# motadora.net
KiCad netlist of a schematic drawn in EAGLE
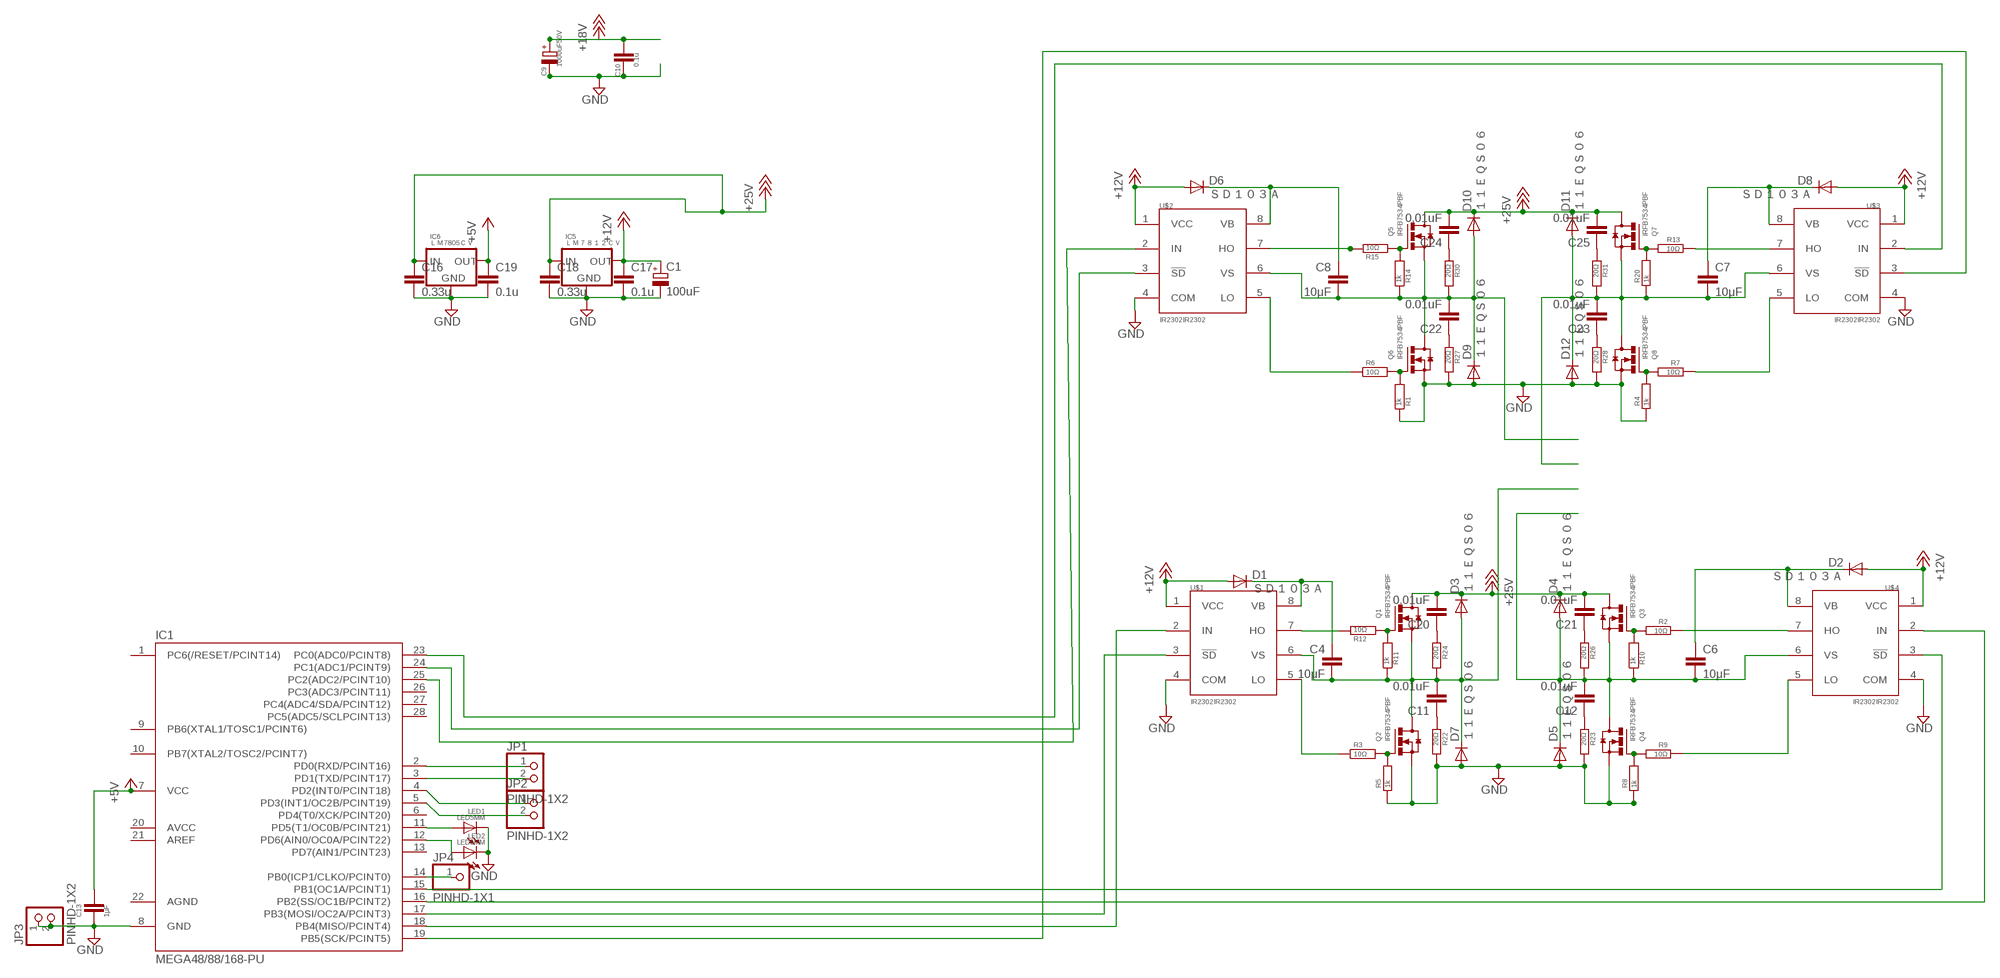
[diagram p0: schematic, sheet 1]

(export (version "E")
  (design (tool "Eeschema 10.0.6"))
  (components
    (comp (ref "C1")
      (value "100uF")
      (footprint "eagle-import:TT2D6")
      (libsource (lib "eagle-import") (part "CPOL-EUTT2D6"))
    )
    (comp (ref "C4")
      (value "10μF")
      (footprint "eagle-import:C025-025X050")
      (libsource (lib "eagle-import") (part "C-EU025-025X050"))
    )
    (comp (ref "C6")
      (value "10μF")
      (footprint "eagle-import:C025-025X050")
      (libsource (lib "eagle-import") (part "C-EU025-025X050"))
    )
    (comp (ref "C7")
      (value "10μF")
      (footprint "eagle-import:C025-025X050")
      (libsource (lib "eagle-import") (part "C-EU025-025X050"))
    )
    (comp (ref "C8")
      (value "10μF")
      (footprint "eagle-import:C025-025X050")
      (libsource (lib "eagle-import") (part "C-EU025-025X050"))
    )
    (comp (ref "C9")
      (value "1000uF50V")
      (footprint "eagle-import:E2,5-7")
      (libsource (lib "eagle-import") (part "CPOL-E2.5-7"))
    )
    (comp (ref "C10")
      (value "0.1u")
      (footprint "eagle-import:C025-025X050")
      (libsource (lib "eagle-import") (part "C-025-025X050"))
    )
    (comp (ref "C11")
      (value "0.01uF")
      (footprint "eagle-import:C025-024X044")
      (libsource (lib "eagle-import") (part "_resistor(抵抗)_C-EU025-024X044"))
    )
    (comp (ref "C12")
      (value "0.01uF")
      (footprint "eagle-import:C025-024X044")
      (libsource (lib "eagle-import") (part "_resistor(抵抗)_C-EU025-024X044"))
    )
    (comp (ref "C13")
      (value "1μF")
      (footprint "eagle-import:C025-025X050")
      (libsource (lib "eagle-import") (part "C{gt}{gt}025-025X050"))
    )
    (comp (ref "C16")
      (value "0.33u")
      (footprint "eagle-import:C025-025X050")
      (libsource (lib "eagle-import") (part "_resistor(抵抗)_C-EU025-025X050"))
    )
    (comp (ref "C17")
      (value "0.1u")
      (footprint "eagle-import:C025-025X050")
      (libsource (lib "eagle-import") (part "_resistor(抵抗)_C-EU025-025X050"))
    )
    (comp (ref "C18")
      (value "0.33u")
      (footprint "eagle-import:C025-025X050")
      (libsource (lib "eagle-import") (part "_resistor(抵抗)_C-EU025-025X050"))
    )
    (comp (ref "C19")
      (value "0.1u")
      (footprint "eagle-import:C025-025X050")
      (libsource (lib "eagle-import") (part "_resistor(抵抗)_C-EU025-025X050"))
    )
    (comp (ref "C20")
      (value "0.01uF")
      (footprint "eagle-import:C025-024X044")
      (libsource (lib "eagle-import") (part "_resistor(抵抗)_C-EU025-024X044"))
    )
    (comp (ref "C21")
      (value "0.01uF")
      (footprint "eagle-import:C025-024X044")
      (libsource (lib "eagle-import") (part "_resistor(抵抗)_C-EU025-024X044"))
    )
    (comp (ref "C22")
      (value "0.01uF")
      (footprint "eagle-import:C025-024X044")
      (libsource (lib "eagle-import") (part "_resistor(抵抗)_C-EU025-024X044"))
    )
    (comp (ref "C23")
      (value "0.01uF")
      (footprint "eagle-import:C025-024X044")
      (libsource (lib "eagle-import") (part "_resistor(抵抗)_C-EU025-024X044"))
    )
    (comp (ref "C24")
      (value "0.01uF")
      (footprint "eagle-import:C025-024X044")
      (libsource (lib "eagle-import") (part "_resistor(抵抗)_C-EU025-024X044"))
    )
    (comp (ref "C25")
      (value "0.01uF")
      (footprint "eagle-import:C025-024X044")
      (libsource (lib "eagle-import") (part "_resistor(抵抗)_C-EU025-024X044"))
    )
    (comp (ref "D1")
      (value "ＳＤ１０３Ａ")
      (footprint "eagle-import:D-5")
      (libsource (lib "eagle-import") (part "DIODE-D-5"))
    )
    (comp (ref "D2")
      (value "ＳＤ１０３Ａ")
      (footprint "eagle-import:D-5")
      (libsource (lib "eagle-import") (part "DIODE-D-5"))
    )
    (comp (ref "D3")
      (value "１１ＥＱＳ０６")
      (footprint "eagle-import:D-5")
      (libsource (lib "eagle-import") (part "DIODE-D-5"))
    )
    (comp (ref "D4")
      (value "１１ＥＱＳ０６")
      (footprint "eagle-import:D-5")
      (libsource (lib "eagle-import") (part "DIODE-D-5"))
    )
    (comp (ref "D5")
      (value "１１ＥＱＳ０６")
      (footprint "eagle-import:D-5")
      (libsource (lib "eagle-import") (part "DIODE-D-5"))
    )
    (comp (ref "D6")
      (value "ＳＤ１０３Ａ")
      (footprint "eagle-import:D-5")
      (libsource (lib "eagle-import") (part "DIODE-D-5"))
    )
    (comp (ref "D7")
      (value "１１ＥＱＳ０６")
      (footprint "eagle-import:D-5")
      (libsource (lib "eagle-import") (part "DIODE-D-5"))
    )
    (comp (ref "D8")
      (value "ＳＤ１０３Ａ")
      (footprint "eagle-import:D-5")
      (libsource (lib "eagle-import") (part "DIODE-D-5"))
    )
    (comp (ref "D9")
      (value "１１ＥＱＳ０６")
      (footprint "eagle-import:D-5")
      (libsource (lib "eagle-import") (part "DIODE-D-5"))
    )
    (comp (ref "D10")
      (value "１１ＥＱＳ０６")
      (footprint "eagle-import:D-5")
      (libsource (lib "eagle-import") (part "DIODE-D-5"))
    )
    (comp (ref "D11")
      (value "１１ＥＱＳ０６")
      (footprint "eagle-import:D-5")
      (libsource (lib "eagle-import") (part "DIODE-D-5"))
    )
    (comp (ref "D12")
      (value "１１ＥＱＳ０６")
      (footprint "eagle-import:D-5")
      (libsource (lib "eagle-import") (part "DIODE-D-5"))
    )
    (comp (ref "IC1")
      (value "MEGA48/88/168-PU")
      (footprint "eagle-import:DIL28-3")
      (libsource (lib "eagle-import") (part "MEGA48/88/168-PU"))
    )
    (comp (ref "IC5")
      (value "ＬＭ７８１２ＣＶ")
      (footprint "eagle-import:TO-92")
      (libsource (lib "eagle-import") (part "V_REG{gt}{gt}TO-92"))
    )
    (comp (ref "IC6")
      (value "ＬＭ7805ＣＶ")
      (footprint "eagle-import:TO-92")
      (libsource (lib "eagle-import") (part "V_REG{gt}{gt}TO-92"))
    )
    (comp (ref "JP1")
      (value "PINHD-1X2")
      (footprint "eagle-import:1X02")
      (libsource (lib "eagle-import") (part "PINHD-1X2"))
    )
    (comp (ref "JP2")
      (value "PINHD-1X2")
      (footprint "eagle-import:1X02")
      (libsource (lib "eagle-import") (part "PINHD-1X2"))
    )
    (comp (ref "JP3")
      (value "PINHD-1X2")
      (footprint "eagle-import:1X02")
      (libsource (lib "eagle-import") (part "PINHD-1X2"))
    )
    (comp (ref "JP4")
      (value "PINHD-1X1")
      (footprint "eagle-import:1X01")
      (libsource (lib "eagle-import") (part "PINHD-1X1"))
    )
    (comp (ref "LED1")
      (value "LED5MM")
      (footprint "eagle-import:LED5MM")
      (libsource (lib "eagle-import") (part "LED5MM"))
    )
    (comp (ref "LED2")
      (value "LED5MM")
      (footprint "eagle-import:LED5MM")
      (libsource (lib "eagle-import") (part "LED5MM"))
    )
    (comp (ref "Q1")
      (value "IRFB7534PBF")
      (footprint "eagle-import:TO220_2")
      (libsource (lib "eagle-import") (part "MOS-FET_NTO-220_2"))
    )
    (comp (ref "Q2")
      (value "IRFB7534PBF")
      (footprint "eagle-import:TO220_2")
      (libsource (lib "eagle-import") (part "MOS-FET_NTO-220_2"))
    )
    (comp (ref "Q3")
      (value "IRFB7534PBF")
      (footprint "eagle-import:TO220_2")
      (libsource (lib "eagle-import") (part "MOS-FET_NTO-220_2"))
    )
    (comp (ref "Q4")
      (value "IRFB7534PBF")
      (footprint "eagle-import:TO220_2")
      (libsource (lib "eagle-import") (part "MOS-FET_NTO-220_2"))
    )
    (comp (ref "Q5")
      (value "IRFB7534PBF")
      (footprint "eagle-import:TO220_2")
      (libsource (lib "eagle-import") (part "MOS-FET_NTO-220_2"))
    )
    (comp (ref "Q6")
      (value "IRFB7534PBF")
      (footprint "eagle-import:TO220_2")
      (libsource (lib "eagle-import") (part "MOS-FET_NTO-220_2"))
    )
    (comp (ref "Q7")
      (value "IRFB7534PBF")
      (footprint "eagle-import:TO220_2")
      (libsource (lib "eagle-import") (part "MOS-FET_NTO-220_2"))
    )
    (comp (ref "Q8")
      (value "IRFB7534PBF")
      (footprint "eagle-import:TO220_2")
      (libsource (lib "eagle-import") (part "MOS-FET_NTO-220_2"))
    )
    (comp (ref "R1")
      (value "1k")
      (footprint "eagle-import:1_4W(8MM)")
      (libsource (lib "eagle-import") (part "R-EU_1/4W(8MM)"))
    )
    (comp (ref "R2")
      (value "10Ω")
      (footprint "eagle-import:1_4W(2.5MM)_")
      (libsource (lib "eagle-import") (part "R-EU_1/4W(2.5MM)_"))
    )
    (comp (ref "R3")
      (value "10Ω")
      (footprint "eagle-import:1_4W(2.5MM)_")
      (libsource (lib "eagle-import") (part "R-EU_1/4W(2.5MM)_"))
    )
    (comp (ref "R4")
      (value "1k")
      (footprint "eagle-import:1_4W(8MM)")
      (libsource (lib "eagle-import") (part "R-EU_1/4W(8MM)"))
    )
    (comp (ref "R5")
      (value "1k")
      (footprint "eagle-import:1_4W(8MM)")
      (libsource (lib "eagle-import") (part "R-EU_1/4W(8MM)"))
    )
    (comp (ref "R6")
      (value "10Ω")
      (footprint "eagle-import:1_4W(2.5MM)_")
      (libsource (lib "eagle-import") (part "R-EU_1/4W(2.5MM)_"))
    )
    (comp (ref "R7")
      (value "10Ω")
      (footprint "eagle-import:1_4W(2.5MM)_")
      (libsource (lib "eagle-import") (part "R-EU_1/4W(2.5MM)_"))
    )
    (comp (ref "R8")
      (value "1k")
      (footprint "eagle-import:1_4W(8MM)")
      (libsource (lib "eagle-import") (part "R-EU_1/4W(8MM)"))
    )
    (comp (ref "R9")
      (value "10Ω")
      (footprint "eagle-import:1_4W(2.5MM)_")
      (libsource (lib "eagle-import") (part "R-EU_1/4W(2.5MM)_"))
    )
    (comp (ref "R10")
      (value "1k")
      (footprint "eagle-import:1_4W(8MM)")
      (libsource (lib "eagle-import") (part "R-EU_1/4W(8MM)"))
    )
    (comp (ref "R11")
      (value "1k")
      (footprint "eagle-import:1_4W(8MM)")
      (libsource (lib "eagle-import") (part "R-EU_1/4W(8MM)"))
    )
    (comp (ref "R12")
      (value "10Ω")
      (footprint "eagle-import:1_4W(2.5MM)_")
      (libsource (lib "eagle-import") (part "R-EU_1/4W(2.5MM)_"))
    )
    (comp (ref "R13")
      (value "10Ω")
      (footprint "eagle-import:1_4W(2.5MM)_")
      (libsource (lib "eagle-import") (part "R-EU_1/4W(2.5MM)_"))
    )
    (comp (ref "R14")
      (value "1k")
      (footprint "eagle-import:1_4W(8MM)")
      (libsource (lib "eagle-import") (part "R-EU_1/4W(8MM)"))
    )
    (comp (ref "R15")
      (value "10Ω")
      (footprint "eagle-import:1_4W(2.5MM)_")
      (libsource (lib "eagle-import") (part "R-EU_1/4W(2.5MM)_"))
    )
    (comp (ref "R20")
      (value "1k")
      (footprint "eagle-import:1_4W(8MM)")
      (libsource (lib "eagle-import") (part "R-EU_1/4W(8MM)"))
    )
    (comp (ref "R22")
      (value "20Ω")
      (footprint "eagle-import:1_4W(2.5MM)_")
      (libsource (lib "eagle-import") (part "R-EU_1/4W(2.5MM)_"))
    )
    (comp (ref "R23")
      (value "20Ω")
      (footprint "eagle-import:1_4W(2.5MM)_")
      (libsource (lib "eagle-import") (part "R-EU_1/4W(2.5MM)_"))
    )
    (comp (ref "R24")
      (value "20Ω")
      (footprint "eagle-import:1_4W(2.5MM)_")
      (libsource (lib "eagle-import") (part "R-EU_1/4W(2.5MM)_"))
    )
    (comp (ref "R26")
      (value "20Ω")
      (footprint "eagle-import:1_4W(2.5MM)_")
      (libsource (lib "eagle-import") (part "R-EU_1/4W(2.5MM)_"))
    )
    (comp (ref "R27")
      (value "20Ω")
      (footprint "eagle-import:1_4W(2.5MM)_")
      (libsource (lib "eagle-import") (part "R-EU_1/4W(2.5MM)_"))
    )
    (comp (ref "R28")
      (value "20Ω")
      (footprint "eagle-import:1_4W(2.5MM)_")
      (libsource (lib "eagle-import") (part "R-EU_1/4W(2.5MM)_"))
    )
    (comp (ref "R30")
      (value "20Ω")
      (footprint "eagle-import:1_4W(2.5MM)_")
      (libsource (lib "eagle-import") (part "R-EU_1/4W(2.5MM)_"))
    )
    (comp (ref "R31")
      (value "20Ω")
      (footprint "eagle-import:1_4W(2.5MM)_")
      (libsource (lib "eagle-import") (part "R-EU_1/4W(2.5MM)_"))
    )
    (comp (ref "U$1")
      (value "IR2302IR2302")
      (footprint "eagle-import:DIL08")
      (libsource (lib "eagle-import") (part "IR2302IR2302"))
    )
    (comp (ref "U$2")
      (value "IR2302IR2302")
      (footprint "eagle-import:DIL08")
      (libsource (lib "eagle-import") (part "IR2302IR2302"))
    )
    (comp (ref "U$3")
      (value "IR2302IR2302")
      (footprint "eagle-import:DIL08")
      (libsource (lib "eagle-import") (part "IR2302IR2302"))
    )
    (comp (ref "U$4")
      (value "IR2302IR2302")
      (footprint "eagle-import:DIL08")
      (libsource (lib "eagle-import") (part "IR2302IR2302"))
    )
  )
  (nets
    (net (code "1") (name "+5V") (class "Default")
      (node (ref "C13") (pin "1") (pinfunction "1_1") (pintype "passive"))
      (node (ref "C19") (pin "1") (pinfunction "1_1") (pintype "passive"))
      (node (ref "IC1") (pin "7") (pinfunction "VCC_7") (pintype "power_in"))
      (node (ref "IC6") (pin "1") (pinfunction "OUT_1") (pintype "passive"))
    )
    (net (code "2") (name "+12V") (class "Default")
      (node (ref "C1") (pin "+") (pinfunction "+_+") (pintype "passive"))
      (node (ref "C17") (pin "1") (pinfunction "1_1") (pintype "passive"))
      (node (ref "D1") (pin "A") (pinfunction "A_A") (pintype "passive"))
      (node (ref "D2") (pin "A") (pinfunction "A_A") (pintype "passive"))
      (node (ref "D6") (pin "A") (pinfunction "A_A") (pintype "passive"))
      (node (ref "D8") (pin "A") (pinfunction "A_A") (pintype "passive"))
      (node (ref "IC5") (pin "1") (pinfunction "OUT_1") (pintype "passive"))
      (node (ref "U$1") (pin "1") (pinfunction "VCC_1") (pintype "bidirectional"))
      (node (ref "U$2") (pin "1") (pinfunction "VCC_1") (pintype "bidirectional"))
      (node (ref "U$3") (pin "1") (pinfunction "VCC_1") (pintype "bidirectional"))
      (node (ref "U$4") (pin "1") (pinfunction "VCC_1") (pintype "bidirectional"))
    )
    (net (code "3") (name "+18V") (class "Default")
      (node (ref "C10") (pin "1") (pinfunction "1_1") (pintype "passive"))
      (node (ref "C16") (pin "1") (pinfunction "1_1") (pintype "passive"))
      (node (ref "C18") (pin "1") (pinfunction "1_1") (pintype "passive"))
      (node (ref "C20") (pin "2") (pinfunction "2_2") (pintype "passive"))
      (node (ref "C21") (pin "2") (pinfunction "2_2") (pintype "passive"))
      (node (ref "C24") (pin "2") (pinfunction "2_2") (pintype "passive"))
      (node (ref "C25") (pin "2") (pinfunction "2_2") (pintype "passive"))
      (node (ref "C9") (pin "+") (pinfunction "+_+") (pintype "passive"))
      (node (ref "D10") (pin "C") (pinfunction "C_C") (pintype "passive"))
      (node (ref "D11") (pin "C") (pinfunction "C_C") (pintype "passive"))
      (node (ref "D3") (pin "C") (pinfunction "C_C") (pintype "passive"))
      (node (ref "D4") (pin "C") (pinfunction "C_C") (pintype "passive"))
      (node (ref "IC5") (pin "3") (pinfunction "IN_3") (pintype "input"))
      (node (ref "IC6") (pin "3") (pinfunction "IN_3") (pintype "input"))
      (node (ref "Q1") (pin "2") (pinfunction "D_2") (pintype "passive"))
      (node (ref "Q3") (pin "2") (pinfunction "D_2") (pintype "passive"))
      (node (ref "Q5") (pin "2") (pinfunction "D_2") (pintype "passive"))
      (node (ref "Q7") (pin "2") (pinfunction "D_2") (pintype "passive"))
    )
    (net (code "4") (name "/AGND") (class "Default")
      (node (ref "IC1") (pin "22") (pinfunction "AGND_22") (pintype "power_in"))
    )
    (net (code "5") (name "GND") (class "Default")
      (node (ref "C1") (pin "-") (pinfunction "-_-") (pintype "passive"))
      (node (ref "C10") (pin "2") (pinfunction "2_2") (pintype "passive"))
      (node (ref "C13") (pin "2") (pinfunction "2_2") (pintype "passive"))
      (node (ref "C16") (pin "2") (pinfunction "2_2") (pintype "passive"))
      (node (ref "C17") (pin "2") (pinfunction "2_2") (pintype "passive"))
      (node (ref "C18") (pin "2") (pinfunction "2_2") (pintype "passive"))
      (node (ref "C19") (pin "2") (pinfunction "2_2") (pintype "passive"))
      (node (ref "C9") (pin "-") (pinfunction "-_-") (pintype "passive"))
      (node (ref "D12") (pin "A") (pinfunction "A_A") (pintype "passive"))
      (node (ref "D5") (pin "A") (pinfunction "A_A") (pintype "passive"))
      (node (ref "D7") (pin "A") (pinfunction "A_A") (pintype "passive"))
      (node (ref "D9") (pin "A") (pinfunction "A_A") (pintype "passive"))
      (node (ref "IC1") (pin "8") (pinfunction "GND_8") (pintype "power_in"))
      (node (ref "IC5") (pin "2") (pinfunction "GND_2") (pintype "input"))
      (node (ref "IC6") (pin "2") (pinfunction "GND_2") (pintype "input"))
      (node (ref "JP3") (pin "1") (pinfunction "1_1") (pintype "passive"))
      (node (ref "JP3") (pin "2") (pinfunction "2_2") (pintype "passive"))
      (node (ref "LED1") (pin "K") (pinfunction "C_K") (pintype "passive"))
      (node (ref "LED2") (pin "K") (pinfunction "C_K") (pintype "passive"))
      (node (ref "Q2") (pin "3") (pinfunction "S_3") (pintype "passive"))
      (node (ref "Q4") (pin "3") (pinfunction "S_3") (pintype "passive"))
      (node (ref "Q6") (pin "3") (pinfunction "S_3") (pintype "passive"))
      (node (ref "Q8") (pin "3") (pinfunction "S_3") (pintype "passive"))
      (node (ref "R1") (pin "1") (pinfunction "1_1") (pintype "passive"))
      (node (ref "R22") (pin "4") (pinfunction "2_4") (pintype "passive"))
      (node (ref "R23") (pin "4") (pinfunction "2_4") (pintype "passive"))
      (node (ref "R27") (pin "4") (pinfunction "2_4") (pintype "passive"))
      (node (ref "R28") (pin "4") (pinfunction "2_4") (pintype "passive"))
      (node (ref "R4") (pin "1") (pinfunction "1_1") (pintype "passive"))
      (node (ref "R5") (pin "1") (pinfunction "1_1") (pintype "passive"))
      (node (ref "R8") (pin "1") (pinfunction "1_1") (pintype "passive"))
      (node (ref "U$1") (pin "4") (pinfunction "COM_4") (pintype "bidirectional"))
      (node (ref "U$2") (pin "4") (pinfunction "COM_4") (pintype "bidirectional"))
      (node (ref "U$3") (pin "4") (pinfunction "COM_4") (pintype "bidirectional"))
      (node (ref "U$4") (pin "4") (pinfunction "COM_4") (pintype "bidirectional"))
    )
    (net (code "6") (name "Net-(IC1-PB0(ICP1{slash}CLKO{slash}PCINT0))") (class "Default")
      (node (ref "IC1") (pin "14") (pinfunction "PB0(ICP1/CLKO/PCINT0)_14") (pintype "bidirectional"))
      (node (ref "JP4") (pin "1") (pinfunction "1_1") (pintype "passive"))
    )
    (net (code "7") (name "Net-(IC1-PB1(OC1A{slash}PCINT1))") (class "Default")
      (node (ref "IC1") (pin "15") (pinfunction "PB1(OC1A/PCINT1)_15") (pintype "bidirectional"))
      (node (ref "U$4") (pin "3") (pinfunction "~{SD}_3") (pintype "bidirectional"))
    )
    (net (code "8") (name "Net-(IC1-PB2(SS{slash}OC1B{slash}PCINT2))") (class "Default")
      (node (ref "IC1") (pin "16") (pinfunction "PB2(SS/OC1B/PCINT2)_16") (pintype "bidirectional"))
      (node (ref "U$4") (pin "2") (pinfunction "IN_2") (pintype "bidirectional"))
    )
    (net (code "9") (name "Net-(IC1-PB3(MOSI{slash}OC2A{slash}PCINT3))") (class "Default")
      (node (ref "IC1") (pin "17") (pinfunction "PB3(MOSI/OC2A/PCINT3)_17") (pintype "bidirectional"))
      (node (ref "U$1") (pin "3") (pinfunction "~{SD}_3") (pintype "bidirectional"))
    )
    (net (code "10") (name "Net-(IC1-PB4(MISO{slash}PCINT4))") (class "Default")
      (node (ref "IC1") (pin "18") (pinfunction "PB4(MISO/PCINT4)_18") (pintype "bidirectional"))
      (node (ref "U$1") (pin "2") (pinfunction "IN_2") (pintype "bidirectional"))
    )
    (net (code "11") (name "Net-(IC1-PB5(SCK{slash}PCINT5))") (class "Default")
      (node (ref "IC1") (pin "19") (pinfunction "PB5(SCK/PCINT5)_19") (pintype "bidirectional"))
      (node (ref "U$3") (pin "3") (pinfunction "~{SD}_3") (pintype "bidirectional"))
    )
    (net (code "12") (name "Net-(IC1-PC0(ADC0{slash}PCINT8))") (class "Default")
      (node (ref "IC1") (pin "23") (pinfunction "PC0(ADC0/PCINT8)_23") (pintype "bidirectional"))
      (node (ref "U$3") (pin "2") (pinfunction "IN_2") (pintype "bidirectional"))
    )
    (net (code "13") (name "Net-(IC1-PC1(ADC1{slash}PCINT9))") (class "Default")
      (node (ref "IC1") (pin "24") (pinfunction "PC1(ADC1/PCINT9)_24") (pintype "bidirectional"))
      (node (ref "U$2") (pin "3") (pinfunction "~{SD}_3") (pintype "bidirectional"))
    )
    (net (code "14") (name "Net-(IC1-PC2(ADC2{slash}PCINT10))") (class "Default")
      (node (ref "IC1") (pin "25") (pinfunction "PC2(ADC2/PCINT10)_25") (pintype "bidirectional"))
      (node (ref "U$2") (pin "2") (pinfunction "IN_2") (pintype "bidirectional"))
    )
    (net (code "15") (name "Net-(IC1-PD0(RXD{slash}PCINT16))") (class "Default")
      (node (ref "IC1") (pin "2") (pinfunction "PD0(RXD/PCINT16)_2") (pintype "bidirectional"))
      (node (ref "JP1") (pin "1") (pinfunction "1_1") (pintype "passive"))
    )
    (net (code "16") (name "Net-(IC1-PD1(TXD{slash}PCINT17))") (class "Default")
      (node (ref "IC1") (pin "3") (pinfunction "PD1(TXD/PCINT17)_3") (pintype "bidirectional"))
      (node (ref "JP1") (pin "2") (pinfunction "2_2") (pintype "passive"))
    )
    (net (code "17") (name "Net-(IC1-PD2(INT0{slash}PCINT18))") (class "Default")
      (node (ref "IC1") (pin "4") (pinfunction "PD2(INT0/PCINT18)_4") (pintype "bidirectional"))
      (node (ref "JP2") (pin "1") (pinfunction "1_1") (pintype "passive"))
    )
    (net (code "18") (name "Net-(IC1-PD3(INT1{slash}OC2B{slash}PCINT19))") (class "Default")
      (node (ref "IC1") (pin "5") (pinfunction "PD3(INT1/OC2B/PCINT19)_5") (pintype "bidirectional"))
      (node (ref "JP2") (pin "2") (pinfunction "2_2") (pintype "passive"))
    )
    (net (code "19") (name "Net-(IC1-PD5(T1{slash}OC0B{slash}PCINT21))") (class "Default")
      (node (ref "IC1") (pin "11") (pinfunction "PD5(T1/OC0B/PCINT21)_11") (pintype "bidirectional"))
      (node (ref "LED1") (pin "A") (pinfunction "A_A") (pintype "passive"))
    )
    (net (code "20") (name "Net-(IC1-PD6(AIN0{slash}OC0A{slash}PCINT22))") (class "Default")
      (node (ref "IC1") (pin "12") (pinfunction "PD6(AIN0/OC0A/PCINT22)_12") (pintype "bidirectional"))
      (node (ref "LED2") (pin "A") (pinfunction "A_A") (pintype "passive"))
    )
    (net (code "21") (name "Net-(Q1-G)") (class "Default")
      (node (ref "Q1") (pin "1") (pinfunction "G_1") (pintype "passive"))
      (node (ref "R11") (pin "2") (pinfunction "2_2") (pintype "passive"))
      (node (ref "R12") (pin "4") (pinfunction "2_4") (pintype "passive"))
    )
    (net (code "22") (name "Net-(Q1-S)") (class "Default")
      (node (ref "C11") (pin "2") (pinfunction "2_2") (pintype "passive"))
      (node (ref "C4") (pin "2") (pinfunction "2_2") (pintype "passive"))
      (node (ref "D3") (pin "A") (pinfunction "A_A") (pintype "passive"))
      (node (ref "D7") (pin "C") (pinfunction "C_C") (pintype "passive"))
      (node (ref "Q1") (pin "3") (pinfunction "S_3") (pintype "passive"))
      (node (ref "Q2") (pin "2") (pinfunction "D_2") (pintype "passive"))
      (node (ref "R11") (pin "1") (pinfunction "1_1") (pintype "passive"))
      (node (ref "R24") (pin "4") (pinfunction "2_4") (pintype "passive"))
      (node (ref "U$1") (pin "6") (pinfunction "VS_6") (pintype "bidirectional"))
    )
    (net (code "23") (name "Net-(Q2-G)") (class "Default")
      (node (ref "Q2") (pin "1") (pinfunction "G_1") (pintype "passive"))
      (node (ref "R3") (pin "4") (pinfunction "2_4") (pintype "passive"))
      (node (ref "R5") (pin "2") (pinfunction "2_2") (pintype "passive"))
    )
    (net (code "24") (name "Net-(Q3-G)") (class "Default")
      (node (ref "Q3") (pin "1") (pinfunction "G_1") (pintype "passive"))
      (node (ref "R10") (pin "2") (pinfunction "2_2") (pintype "passive"))
      (node (ref "R2") (pin "4") (pinfunction "2_4") (pintype "passive"))
    )
    (net (code "25") (name "Net-(Q3-S)") (class "Default")
      (node (ref "C12") (pin "2") (pinfunction "2_2") (pintype "passive"))
      (node (ref "C6") (pin "2") (pinfunction "2_2") (pintype "passive"))
      (node (ref "D4") (pin "A") (pinfunction "A_A") (pintype "passive"))
      (node (ref "D5") (pin "C") (pinfunction "C_C") (pintype "passive"))
      (node (ref "Q3") (pin "3") (pinfunction "S_3") (pintype "passive"))
      (node (ref "Q4") (pin "2") (pinfunction "D_2") (pintype "passive"))
      (node (ref "R10") (pin "1") (pinfunction "1_1") (pintype "passive"))
      (node (ref "R26") (pin "4") (pinfunction "2_4") (pintype "passive"))
      (node (ref "U$4") (pin "6") (pinfunction "VS_6") (pintype "bidirectional"))
    )
    (net (code "26") (name "Net-(Q4-G)") (class "Default")
      (node (ref "Q4") (pin "1") (pinfunction "G_1") (pintype "passive"))
      (node (ref "R8") (pin "2") (pinfunction "2_2") (pintype "passive"))
      (node (ref "R9") (pin "4") (pinfunction "2_4") (pintype "passive"))
    )
    (net (code "27") (name "Net-(Q5-G)") (class "Default")
      (node (ref "Q5") (pin "1") (pinfunction "G_1") (pintype "passive"))
      (node (ref "R14") (pin "2") (pinfunction "2_2") (pintype "passive"))
      (node (ref "R15") (pin "4") (pinfunction "2_4") (pintype "passive"))
    )
    (net (code "28") (name "Net-(Q5-S)") (class "Default")
      (node (ref "C22") (pin "2") (pinfunction "2_2") (pintype "passive"))
      (node (ref "C8") (pin "2") (pinfunction "2_2") (pintype "passive"))
      (node (ref "D10") (pin "A") (pinfunction "A_A") (pintype "passive"))
      (node (ref "D9") (pin "C") (pinfunction "C_C") (pintype "passive"))
      (node (ref "Q5") (pin "3") (pinfunction "S_3") (pintype "passive"))
      (node (ref "Q6") (pin "2") (pinfunction "D_2") (pintype "passive"))
      (node (ref "R14") (pin "1") (pinfunction "1_1") (pintype "passive"))
      (node (ref "R30") (pin "4") (pinfunction "2_4") (pintype "passive"))
      (node (ref "U$2") (pin "6") (pinfunction "VS_6") (pintype "bidirectional"))
    )
    (net (code "29") (name "Net-(Q6-G)") (class "Default")
      (node (ref "Q6") (pin "1") (pinfunction "G_1") (pintype "passive"))
      (node (ref "R1") (pin "2") (pinfunction "2_2") (pintype "passive"))
      (node (ref "R6") (pin "4") (pinfunction "2_4") (pintype "passive"))
    )
    (net (code "30") (name "Net-(Q7-G)") (class "Default")
      (node (ref "Q7") (pin "1") (pinfunction "G_1") (pintype "passive"))
      (node (ref "R13") (pin "4") (pinfunction "2_4") (pintype "passive"))
      (node (ref "R20") (pin "2") (pinfunction "2_2") (pintype "passive"))
    )
    (net (code "31") (name "Net-(Q7-S)") (class "Default")
      (node (ref "C23") (pin "2") (pinfunction "2_2") (pintype "passive"))
      (node (ref "C7") (pin "2") (pinfunction "2_2") (pintype "passive"))
      (node (ref "D11") (pin "A") (pinfunction "A_A") (pintype "passive"))
      (node (ref "D12") (pin "C") (pinfunction "C_C") (pintype "passive"))
      (node (ref "Q7") (pin "3") (pinfunction "S_3") (pintype "passive"))
      (node (ref "Q8") (pin "2") (pinfunction "D_2") (pintype "passive"))
      (node (ref "R20") (pin "1") (pinfunction "1_1") (pintype "passive"))
      (node (ref "R31") (pin "4") (pinfunction "2_4") (pintype "passive"))
      (node (ref "U$3") (pin "6") (pinfunction "VS_6") (pintype "bidirectional"))
    )
    (net (code "32") (name "Net-(Q8-G)") (class "Default")
      (node (ref "Q8") (pin "1") (pinfunction "G_1") (pintype "passive"))
      (node (ref "R4") (pin "2") (pinfunction "2_2") (pintype "passive"))
      (node (ref "R7") (pin "4") (pinfunction "2_4") (pintype "passive"))
    )
    (net (code "33") (name "Net-(R2-1)") (class "Default")
      (node (ref "R2") (pin "3") (pinfunction "1_3") (pintype "passive"))
      (node (ref "U$4") (pin "7") (pinfunction "HO_7") (pintype "bidirectional"))
    )
    (net (code "34") (name "Net-(R3-1)") (class "Default")
      (node (ref "R3") (pin "3") (pinfunction "1_3") (pintype "passive"))
      (node (ref "U$1") (pin "5") (pinfunction "LO_5") (pintype "bidirectional"))
    )
    (net (code "35") (name "Net-(R6-1)") (class "Default")
      (node (ref "R6") (pin "3") (pinfunction "1_3") (pintype "passive"))
      (node (ref "U$2") (pin "5") (pinfunction "LO_5") (pintype "bidirectional"))
    )
    (net (code "36") (name "Net-(R7-1)") (class "Default")
      (node (ref "R7") (pin "3") (pinfunction "1_3") (pintype "passive"))
      (node (ref "U$3") (pin "5") (pinfunction "LO_5") (pintype "bidirectional"))
    )
    (net (code "37") (name "Net-(R9-1)") (class "Default")
      (node (ref "R9") (pin "3") (pinfunction "1_3") (pintype "passive"))
      (node (ref "U$4") (pin "5") (pinfunction "LO_5") (pintype "bidirectional"))
    )
    (net (code "38") (name "Net-(R12-1)") (class "Default")
      (node (ref "R12") (pin "3") (pinfunction "1_3") (pintype "passive"))
      (node (ref "U$1") (pin "7") (pinfunction "HO_7") (pintype "bidirectional"))
    )
    (net (code "39") (name "Net-(R13-1)") (class "Default")
      (node (ref "R13") (pin "3") (pinfunction "1_3") (pintype "passive"))
      (node (ref "U$3") (pin "7") (pinfunction "HO_7") (pintype "bidirectional"))
    )
    (net (code "40") (name "Net-(R15-1)") (class "Default")
      (node (ref "R15") (pin "3") (pinfunction "1_3") (pintype "passive"))
      (node (ref "U$2") (pin "7") (pinfunction "HO_7") (pintype "bidirectional"))
    )
    (net (code "41") (name "Net-(R22-1)") (class "Default")
      (node (ref "C11") (pin "1") (pinfunction "1_1") (pintype "passive"))
      (node (ref "R22") (pin "3") (pinfunction "1_3") (pintype "passive"))
    )
    (net (code "42") (name "Net-(R23-1)") (class "Default")
      (node (ref "C12") (pin "1") (pinfunction "1_1") (pintype "passive"))
      (node (ref "R23") (pin "3") (pinfunction "1_3") (pintype "passive"))
    )
    (net (code "43") (name "Net-(R24-1)") (class "Default")
      (node (ref "C20") (pin "1") (pinfunction "1_1") (pintype "passive"))
      (node (ref "R24") (pin "3") (pinfunction "1_3") (pintype "passive"))
    )
    (net (code "44") (name "Net-(R26-1)") (class "Default")
      (node (ref "C21") (pin "1") (pinfunction "1_1") (pintype "passive"))
      (node (ref "R26") (pin "3") (pinfunction "1_3") (pintype "passive"))
    )
    (net (code "45") (name "Net-(R27-1)") (class "Default")
      (node (ref "C22") (pin "1") (pinfunction "1_1") (pintype "passive"))
      (node (ref "R27") (pin "3") (pinfunction "1_3") (pintype "passive"))
    )
    (net (code "46") (name "Net-(R28-1)") (class "Default")
      (node (ref "C23") (pin "1") (pinfunction "1_1") (pintype "passive"))
      (node (ref "R28") (pin "3") (pinfunction "1_3") (pintype "passive"))
    )
    (net (code "47") (name "Net-(R30-1)") (class "Default")
      (node (ref "C24") (pin "1") (pinfunction "1_1") (pintype "passive"))
      (node (ref "R30") (pin "3") (pinfunction "1_3") (pintype "passive"))
    )
    (net (code "48") (name "Net-(R31-1)") (class "Default")
      (node (ref "C25") (pin "1") (pinfunction "1_1") (pintype "passive"))
      (node (ref "R31") (pin "3") (pinfunction "1_3") (pintype "passive"))
    )
    (net (code "49") (name "Net-(U$1-VB)") (class "Default")
      (node (ref "C4") (pin "1") (pinfunction "1_1") (pintype "passive"))
      (node (ref "D1") (pin "C") (pinfunction "C_C") (pintype "passive"))
      (node (ref "U$1") (pin "8") (pinfunction "VB_8") (pintype "bidirectional"))
    )
    (net (code "50") (name "Net-(U$2-VB)") (class "Default")
      (node (ref "C8") (pin "1") (pinfunction "1_1") (pintype "passive"))
      (node (ref "D6") (pin "C") (pinfunction "C_C") (pintype "passive"))
      (node (ref "U$2") (pin "8") (pinfunction "VB_8") (pintype "bidirectional"))
    )
    (net (code "51") (name "Net-(U$3-VB)") (class "Default")
      (node (ref "C7") (pin "1") (pinfunction "1_1") (pintype "passive"))
      (node (ref "D8") (pin "C") (pinfunction "C_C") (pintype "passive"))
      (node (ref "U$3") (pin "8") (pinfunction "VB_8") (pintype "bidirectional"))
    )
    (net (code "52") (name "Net-(U$4-VB)") (class "Default")
      (node (ref "C6") (pin "1") (pinfunction "1_1") (pintype "passive"))
      (node (ref "D2") (pin "C") (pinfunction "C_C") (pintype "passive"))
      (node (ref "U$4") (pin "8") (pinfunction "VB_8") (pintype "bidirectional"))
    )
    (net (code "53") (name "unconnected-(IC1-AREF-Pad21)") (class "Default")
      (node (ref "IC1") (pin "21") (pinfunction "AREF_21") (pintype "passive"))
    )
    (net (code "54") (name "unconnected-(IC1-AVCC-Pad20)") (class "Default")
      (node (ref "IC1") (pin "20") (pinfunction "AVCC_20") (pintype "passive"))
    )
    (net (code "55") (name "unconnected-(IC1-PB6(XTAL1{slash}TOSC1{slash}PCINT6)-Pad9)") (class "Default")
      (node (ref "IC1") (pin "9") (pinfunction "PB6(XTAL1/TOSC1/PCINT6)_9") (pintype "bidirectional"))
    )
    (net (code "56") (name "unconnected-(IC1-PB7(XTAL2{slash}TOSC2{slash}PCINT7)-Pad10)") (class "Default")
      (node (ref "IC1") (pin "10") (pinfunction "PB7(XTAL2/TOSC2/PCINT7)_10") (pintype "bidirectional"))
    )
    (net (code "57") (name "unconnected-(IC1-PC3(ADC3{slash}PCINT11)-Pad26)") (class "Default")
      (node (ref "IC1") (pin "26") (pinfunction "PC3(ADC3/PCINT11)_26") (pintype "bidirectional"))
    )
    (net (code "58") (name "unconnected-(IC1-PC4(ADC4{slash}SDA{slash}PCINT12)-Pad27)") (class "Default")
      (node (ref "IC1") (pin "27") (pinfunction "PC4(ADC4/SDA/PCINT12)_27") (pintype "bidirectional"))
    )
    (net (code "59") (name "unconnected-(IC1-PC5(ADC5{slash}SCLPCINT13)-Pad28)") (class "Default")
      (node (ref "IC1") (pin "28") (pinfunction "PC5(ADC5/SCLPCINT13)_28") (pintype "bidirectional"))
    )
    (net (code "60") (name "unconnected-(IC1-PC6({slash}RESET{slash}PCINT14)-Pad1)") (class "Default")
      (node (ref "IC1") (pin "1") (pinfunction "PC6(/RESET/PCINT14)_1") (pintype "bidirectional"))
    )
    (net (code "61") (name "unconnected-(IC1-PD4(T0{slash}XCK{slash}PCINT20)-Pad6)") (class "Default")
      (node (ref "IC1") (pin "6") (pinfunction "PD4(T0/XCK/PCINT20)_6") (pintype "bidirectional"))
    )
    (net (code "62") (name "unconnected-(IC1-PD7(AIN1{slash}PCINT23)-Pad13)") (class "Default")
      (node (ref "IC1") (pin "13") (pinfunction "PD7(AIN1/PCINT23)_13") (pintype "bidirectional"))
    )
  )
)
